# WikiHub-Mini.net
KiCad netlist of a schematic drawn in Altium Designer
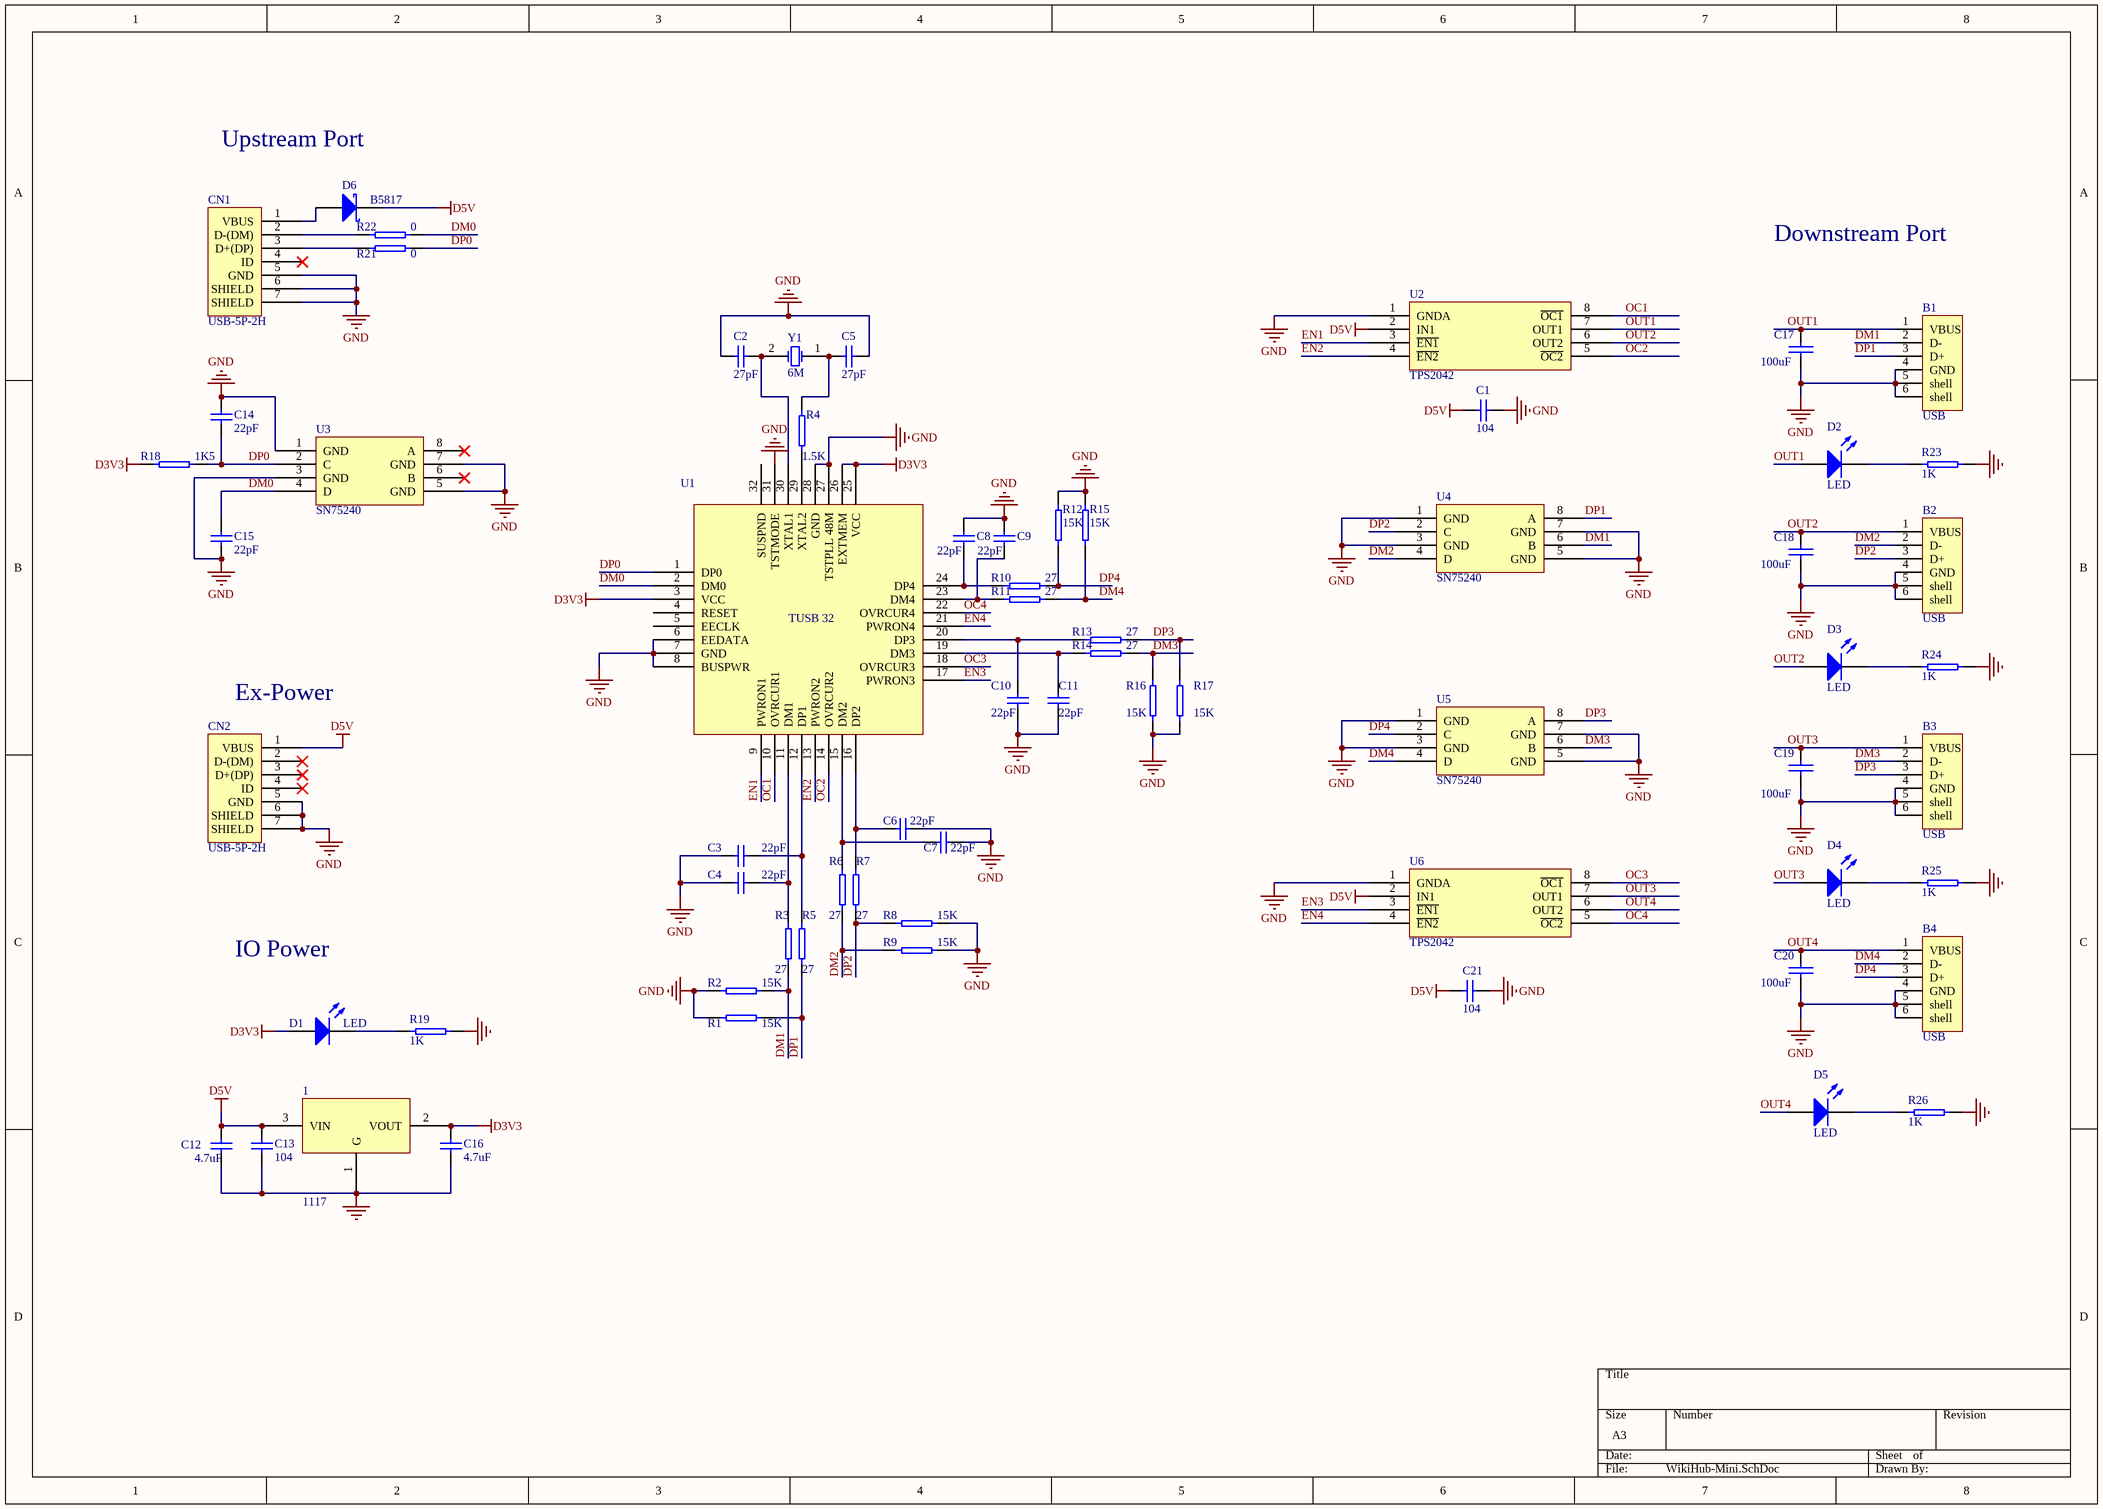
[diagram p0: WikiHub-Mini.SchDoc]

(export (version "E")
  (design (tool "Eeschema 10.0.6"))
  (components
    (comp (ref "1") (value "1117") (footprint "1117") (libsource (lib "原理图封装库") (part "117")))
    (comp (ref "B1") (value "USB") (footprint "USB-A-Female-T2-Lite") (libsource (lib "*") (part "USB")))
    (comp (ref "B2") (value "USB") (footprint "USB-A-Female-T2-Lite") (libsource (lib "*") (part "USB")))
    (comp (ref "B3") (value "USB") (footprint "USB-A-Female-T2-Lite") (libsource (lib "*") (part "USB")))
    (comp (ref "B4") (value "USB") (footprint "USB-A-Female-T2-Lite") (libsource (lib "*") (part "USB")))
    (comp (ref "C1")
      (value "104")
      (footprint "C0603L")
      (description "Capacitor")
      (fields (field (name "Comment") "Cap") (field (name "PUBLISHER") "Altium Limited"))
      (libsource (lib "Miscellaneous Devices") (part "Cap"))
    )
    (comp (ref "C2")
      (value "27pF")
      (footprint "C0603L")
      (description "Capacitor")
      (fields (field (name "PUBLISHER") "Altium Limited"))
      (libsource (lib "Miscellaneous Devices") (part "Cap"))
    )
    (comp (ref "C3")
      (value "22pF")
      (footprint "C0603L")
      (description "Capacitor")
      (fields (field (name "PUBLISHER") "Altium Limited"))
      (libsource (lib "Miscellaneous Devices") (part "Cap"))
    )
    (comp (ref "C4")
      (value "22pF")
      (footprint "C0603L")
      (description "Capacitor")
      (fields (field (name "PUBLISHER") "Altium Limited"))
      (libsource (lib "Miscellaneous Devices") (part "Cap"))
    )
    (comp (ref "C5")
      (value "27pF")
      (footprint "C0603L")
      (description "Capacitor")
      (fields (field (name "PUBLISHER") "Altium Limited"))
      (libsource (lib "Miscellaneous Devices") (part "Cap"))
    )
    (comp (ref "C6")
      (value "22pF")
      (footprint "C0603L")
      (description "Capacitor")
      (fields (field (name "PUBLISHER") "Altium Limited"))
      (libsource (lib "Miscellaneous Devices") (part "Cap"))
    )
    (comp (ref "C7")
      (value "22pF")
      (footprint "C0603L")
      (description "Capacitor")
      (fields (field (name "PUBLISHER") "Altium Limited"))
      (libsource (lib "Miscellaneous Devices") (part "Cap"))
    )
    (comp (ref "C8")
      (value "22pF")
      (footprint "C0603L")
      (description "Capacitor")
      (fields (field (name "PUBLISHER") "Altium Limited"))
      (libsource (lib "Miscellaneous Devices") (part "Cap"))
    )
    (comp (ref "C9")
      (value "22pF")
      (footprint "C0603L")
      (description "Capacitor")
      (fields (field (name "PUBLISHER") "Altium Limited"))
      (libsource (lib "Miscellaneous Devices") (part "Cap"))
    )
    (comp (ref "C10")
      (value "22pF")
      (footprint "C0603L")
      (description "Capacitor")
      (fields (field (name "PUBLISHER") "Altium Limited"))
      (libsource (lib "Miscellaneous Devices") (part "Cap"))
    )
    (comp (ref "C11")
      (value "22pF")
      (footprint "C0603L")
      (description "Capacitor")
      (fields (field (name "PUBLISHER") "Altium Limited"))
      (libsource (lib "Miscellaneous Devices") (part "Cap"))
    )
    (comp (ref "C12")
      (value "4.7uF")
      (footprint "C0603L")
      (description "Capacitor")
      (fields (field (name "Comment") "Cap") (field (name "PUBLISHER") "Altium Limited"))
      (libsource (lib "Miscellaneous Devices") (part "Cap"))
    )
    (comp (ref "C13")
      (value "104")
      (footprint "C0603L")
      (description "Capacitor")
      (fields (field (name "Comment") "Cap") (field (name "PUBLISHER") "Altium Limited"))
      (libsource (lib "Miscellaneous Devices") (part "Cap"))
    )
    (comp (ref "C14")
      (value "22pF")
      (footprint "C0603L")
      (description "Capacitor")
      (fields (field (name "PUBLISHER") "Altium Limited"))
      (libsource (lib "Miscellaneous Devices") (part "Cap"))
    )
    (comp (ref "C15")
      (value "22pF")
      (footprint "C0603L")
      (description "Capacitor")
      (fields (field (name "PUBLISHER") "Altium Limited"))
      (libsource (lib "Miscellaneous Devices") (part "Cap"))
    )
    (comp (ref "C16")
      (value "4.7uF")
      (footprint "C0603L")
      (description "Capacitor")
      (fields (field (name "Comment") "Cap") (field (name "PUBLISHER") "Altium Limited"))
      (libsource (lib "Miscellaneous Devices") (part "Cap"))
    )
    (comp (ref "C17")
      (value "100uF")
      (footprint "1210")
      (description "Capacitor")
      (libsource (lib "*") (part "CAP"))
    )
    (comp (ref "C18")
      (value "100uF")
      (footprint "1210")
      (description "Capacitor")
      (libsource (lib "*") (part "CAP"))
    )
    (comp (ref "C19")
      (value "100uF")
      (footprint "1210")
      (description "Capacitor")
      (libsource (lib "*") (part "CAP"))
    )
    (comp (ref "C20")
      (value "100uF")
      (footprint "1210")
      (description "Capacitor")
      (libsource (lib "*") (part "CAP"))
    )
    (comp (ref "C21")
      (value "104")
      (footprint "C0603L")
      (description "Capacitor")
      (fields (field (name "Comment") "Cap") (field (name "PUBLISHER") "Altium Limited"))
      (libsource (lib "Miscellaneous Devices") (part "Cap"))
    )
    (comp (ref "CN1")
      (value "USB-5P-2H")
      (footprint "USB-B-MICRO-Female-T3")
      (description "USB-M5P-2H")
      (libsource (lib "USB") (part "USB-5P-2H"))
    )
    (comp (ref "CN2")
      (value "USB-5P-2H")
      (footprint "USB-B-MICRO-Female-T3")
      (description "USB-M5P-2H")
      (libsource (lib "USB") (part "USB-5P-2H"))
    )
    (comp (ref "D1")
      (value "LED")
      (footprint "0603pn")
      (description "Typical INFRARED GaAs LED")
      (fields (field (name "PUBLISHER") "Altium Limited"))
      (libsource (lib "Miscellaneous Devices") (part "LED0"))
    )
    (comp (ref "D2")
      (value "LED")
      (footprint "0603pn")
      (description "Typical INFRARED GaAs LED")
      (fields (field (name "PUBLISHER") "Altium Limited"))
      (libsource (lib "Miscellaneous Devices") (part "LED0"))
    )
    (comp (ref "D3")
      (value "LED")
      (footprint "0603pn")
      (description "Typical INFRARED GaAs LED")
      (fields (field (name "PUBLISHER") "Altium Limited"))
      (libsource (lib "Miscellaneous Devices") (part "LED0"))
    )
    (comp (ref "D4")
      (value "LED")
      (footprint "0603pn")
      (description "Typical INFRARED GaAs LED")
      (fields (field (name "PUBLISHER") "Altium Limited"))
      (libsource (lib "Miscellaneous Devices") (part "LED0"))
    )
    (comp (ref "D5")
      (value "LED")
      (footprint "0603pn")
      (description "Typical INFRARED GaAs LED")
      (fields (field (name "PUBLISHER") "Altium Limited"))
      (libsource (lib "Miscellaneous Devices") (part "LED0"))
    )
    (comp (ref "D6")
      (value "B5817")
      (footprint "SOD-123")
      (description "Schottky Diode")
      (fields (field (name "PUBLISHER") "Altium Limited"))
      (libsource (lib "Misc") (part "D Schottky"))
    )
    (comp (ref "R1") (value "15K") (footprint "R0603") (libsource (lib "原理图封装库") (part "RES")))
    (comp (ref "R2") (value "15K") (footprint "R0603") (libsource (lib "原理图封装库") (part "RES")))
    (comp (ref "R3") (value "27") (footprint "R0603") (libsource (lib "原理图封装库") (part "RES")))
    (comp (ref "R4") (value "1.5K") (footprint "R0603") (libsource (lib "原理图封装库") (part "RES")))
    (comp (ref "R5") (value "27") (footprint "R0603") (libsource (lib "原理图封装库") (part "RES")))
    (comp (ref "R6") (value "27") (footprint "R0603") (libsource (lib "原理图封装库") (part "RES")))
    (comp (ref "R7") (value "27") (footprint "R0603") (libsource (lib "原理图封装库") (part "RES")))
    (comp (ref "R8") (value "15K") (footprint "R0603") (libsource (lib "原理图封装库") (part "RES")))
    (comp (ref "R9") (value "15K") (footprint "R0603") (libsource (lib "原理图封装库") (part "RES")))
    (comp (ref "R10") (value "27") (footprint "R0603") (libsource (lib "原理图封装库") (part "RES")))
    (comp (ref "R11") (value "27") (footprint "R0603") (libsource (lib "原理图封装库") (part "RES")))
    (comp (ref "R12") (value "15K") (footprint "R0603") (libsource (lib "原理图封装库") (part "RES")))
    (comp (ref "R13") (value "27") (footprint "R0603") (libsource (lib "原理图封装库") (part "RES")))
    (comp (ref "R14") (value "27") (footprint "R0603") (libsource (lib "原理图封装库") (part "RES")))
    (comp (ref "R15") (value "15K") (footprint "R0603") (libsource (lib "原理图封装库") (part "RES")))
    (comp (ref "R16") (value "15K") (footprint "R0603") (libsource (lib "原理图封装库") (part "RES")))
    (comp (ref "R17") (value "15K") (footprint "R0603") (libsource (lib "原理图封装库") (part "RES")))
    (comp (ref "R18") (value "1K5") (footprint "R0603") (libsource (lib "原理图封装库") (part "RES")))
    (comp (ref "R19") (value "1K") (footprint "R0603") (libsource (lib "原理图封装库") (part "RES")))
    (comp (ref "R21") (value "0") (footprint "R0603") (libsource (lib "原理图封装库") (part "RES")))
    (comp (ref "R22") (value "0") (footprint "R0603") (libsource (lib "原理图封装库") (part "RES")))
    (comp (ref "R23") (value "1K") (footprint "R0603") (libsource (lib "原理图封装库") (part "RES")))
    (comp (ref "R24") (value "1K") (footprint "R0603") (libsource (lib "原理图封装库") (part "RES")))
    (comp (ref "R25") (value "1K") (footprint "R0603") (libsource (lib "原理图封装库") (part "RES")))
    (comp (ref "R26") (value "1K") (footprint "R0603") (libsource (lib "原理图封装库") (part "RES")))
    (comp (ref "U1") (value "TUSB 32") (footprint "TQFP32") (libsource (lib "rhyme-SCH") (part "TUSB 32")))
    (comp (ref "U2") (value "TPS2042") (footprint "SO8W_M") (libsource (lib "WikiHub") (part "TPS2042")))
    (comp (ref "U3")
      (value "SN75240")
      (footprint "SOP8 - 0.65")
      (libsource (lib "rhyme-SCH") (part "SN75240"))
    )
    (comp (ref "U4")
      (value "SN75240")
      (footprint "SOP8 - 0.65")
      (libsource (lib "rhyme-SCH") (part "SN75240"))
    )
    (comp (ref "U5")
      (value "SN75240")
      (footprint "SOP8 - 0.65")
      (libsource (lib "rhyme-SCH") (part "SN75240"))
    )
    (comp (ref "U6") (value "TPS2042") (footprint "SO8W_M") (libsource (lib "WikiHub") (part "TPS2042")))
    (comp (ref "Y1")
      (value "6M")
      (footprint "XTAL")
      (description "Crystal Oscillator")
      (fields (field (name "PUBLISHER") "Altium Limited"))
      (libsource (lib "Miscellaneous Devices") (part "XTAL"))
    )
  )
  (nets
    (net (code "1") (name "/DM0") (class "Default")
      (node (ref "C15") (pin "1") (pinfunction "1_1") (pintype "passive"))
      (node (ref "R22") (pin "1") (pinfunction "1_1") (pintype "passive"))
      (node (ref "U1") (pin "2") (pinfunction "DM0_2") (pintype "passive"))
      (node (ref "U3") (pin "4") (pinfunction "D_4") (pintype "passive"))
    )
    (net (code "2") (name "/DM1") (class "Default")
      (node (ref "B1") (pin "2") (pinfunction "D-_2") (pintype "passive"))
      (node (ref "R2") (pin "1") (pinfunction "1_1") (pintype "passive"))
      (node (ref "R3") (pin "1") (pinfunction "1_1") (pintype "passive"))
      (node (ref "U4") (pin "6") (pinfunction "B_6") (pintype "passive"))
    )
    (net (code "3") (name "/DM2") (class "Default")
      (node (ref "B2") (pin "2") (pinfunction "D-_2") (pintype "passive"))
      (node (ref "R6") (pin "1") (pinfunction "1_1") (pintype "passive"))
      (node (ref "R9") (pin "2") (pinfunction "2_2") (pintype "passive"))
      (node (ref "U4") (pin "4") (pinfunction "D_4") (pintype "passive"))
    )
    (net (code "4") (name "/DM3") (class "Default")
      (node (ref "B3") (pin "2") (pinfunction "D-_2") (pintype "passive"))
      (node (ref "R14") (pin "1") (pinfunction "1_1") (pintype "passive"))
      (node (ref "R16") (pin "1") (pinfunction "1_1") (pintype "passive"))
      (node (ref "U5") (pin "6") (pinfunction "B_6") (pintype "passive"))
    )
    (net (code "5") (name "/DM4") (class "Default")
      (node (ref "B4") (pin "2") (pinfunction "D-_2") (pintype "passive"))
      (node (ref "R11") (pin "1") (pinfunction "1_1") (pintype "passive"))
      (node (ref "R15") (pin "2") (pinfunction "2_2") (pintype "passive"))
      (node (ref "U5") (pin "4") (pinfunction "D_4") (pintype "passive"))
    )
    (net (code "6") (name "/DP0") (class "Default")
      (node (ref "C14") (pin "2") (pinfunction "2_2") (pintype "passive"))
      (node (ref "R18") (pin "1") (pinfunction "1_1") (pintype "passive"))
      (node (ref "R21") (pin "1") (pinfunction "1_1") (pintype "passive"))
      (node (ref "U1") (pin "1") (pinfunction "DP0_1") (pintype "passive"))
      (node (ref "U3") (pin "2") (pinfunction "C_2") (pintype "passive"))
    )
    (net (code "7") (name "/DP1") (class "Default")
      (node (ref "B1") (pin "3") (pinfunction "D+_3") (pintype "passive"))
      (node (ref "R1") (pin "1") (pinfunction "1_1") (pintype "passive"))
      (node (ref "R5") (pin "1") (pinfunction "1_1") (pintype "passive"))
      (node (ref "U4") (pin "8") (pinfunction "A_8") (pintype "passive"))
    )
    (net (code "8") (name "/DP2") (class "Default")
      (node (ref "B2") (pin "3") (pinfunction "D+_3") (pintype "passive"))
      (node (ref "R7") (pin "1") (pinfunction "1_1") (pintype "passive"))
      (node (ref "R8") (pin "2") (pinfunction "2_2") (pintype "passive"))
      (node (ref "U4") (pin "2") (pinfunction "C_2") (pintype "passive"))
    )
    (net (code "9") (name "/DP3") (class "Default")
      (node (ref "B3") (pin "3") (pinfunction "D+_3") (pintype "passive"))
      (node (ref "R13") (pin "1") (pinfunction "1_1") (pintype "passive"))
      (node (ref "R17") (pin "1") (pinfunction "1_1") (pintype "passive"))
      (node (ref "U5") (pin "8") (pinfunction "A_8") (pintype "passive"))
    )
    (net (code "10") (name "/DP4") (class "Default")
      (node (ref "B4") (pin "3") (pinfunction "D+_3") (pintype "passive"))
      (node (ref "R10") (pin "1") (pinfunction "1_1") (pintype "passive"))
      (node (ref "R12") (pin "2") (pinfunction "2_2") (pintype "passive"))
      (node (ref "U5") (pin "2") (pinfunction "C_2") (pintype "passive"))
    )
    (net (code "11") (name "/EN1") (class "Default")
      (node (ref "U1") (pin "9") (pinfunction "PWRON1_9") (pintype "passive"))
      (node (ref "U2") (pin "3") (pinfunction "~{EN1}_3") (pintype "passive"))
    )
    (net (code "12") (name "/EN2") (class "Default")
      (node (ref "U1") (pin "13") (pinfunction "PWRON2_13") (pintype "passive"))
      (node (ref "U2") (pin "4") (pinfunction "~{EN2}_4") (pintype "passive"))
    )
    (net (code "13") (name "/EN3") (class "Default")
      (node (ref "U1") (pin "17") (pinfunction "PWRON3_17") (pintype "passive"))
      (node (ref "U6") (pin "3") (pinfunction "~{EN1}_3") (pintype "passive"))
    )
    (net (code "14") (name "/EN4") (class "Default")
      (node (ref "U1") (pin "21") (pinfunction "PWRON4_21") (pintype "passive"))
      (node (ref "U6") (pin "4") (pinfunction "~{EN2}_4") (pintype "passive"))
    )
    (net (code "15") (name "/OC1") (class "Default")
      (node (ref "U1") (pin "10") (pinfunction "OVRCUR1_10") (pintype "passive"))
      (node (ref "U2") (pin "8") (pinfunction "~{OC1}_8") (pintype "passive"))
    )
    (net (code "16") (name "/OC2") (class "Default")
      (node (ref "U1") (pin "14") (pinfunction "OVRCUR2_14") (pintype "passive"))
      (node (ref "U2") (pin "5") (pinfunction "~{OC2}_5") (pintype "passive"))
    )
    (net (code "17") (name "/OC3") (class "Default")
      (node (ref "U1") (pin "18") (pinfunction "OVRCUR3_18") (pintype "passive"))
      (node (ref "U6") (pin "8") (pinfunction "~{OC1}_8") (pintype "passive"))
    )
    (net (code "18") (name "/OC4") (class "Default")
      (node (ref "U1") (pin "22") (pinfunction "OVRCUR4_22") (pintype "passive"))
      (node (ref "U6") (pin "5") (pinfunction "~{OC2}_5") (pintype "passive"))
    )
    (net (code "19") (name "/OUT1") (class "Default")
      (node (ref "B1") (pin "1") (pinfunction "VBUS_1") (pintype "passive"))
      (node (ref "C17") (pin "1") (pinfunction "1_1") (pintype "passive"))
      (node (ref "D2") (pin "1") (pinfunction "A_1") (pintype "passive"))
      (node (ref "U2") (pin "7") (pinfunction "OUT1_7") (pintype "passive"))
    )
    (net (code "20") (name "/OUT2") (class "Default")
      (node (ref "B2") (pin "1") (pinfunction "VBUS_1") (pintype "passive"))
      (node (ref "C18") (pin "1") (pinfunction "1_1") (pintype "passive"))
      (node (ref "D3") (pin "1") (pinfunction "A_1") (pintype "passive"))
      (node (ref "U2") (pin "6") (pinfunction "OUT2_6") (pintype "passive"))
    )
    (net (code "21") (name "/OUT3") (class "Default")
      (node (ref "B3") (pin "1") (pinfunction "VBUS_1") (pintype "passive"))
      (node (ref "C19") (pin "1") (pinfunction "1_1") (pintype "passive"))
      (node (ref "D4") (pin "1") (pinfunction "A_1") (pintype "passive"))
      (node (ref "U6") (pin "7") (pinfunction "OUT1_7") (pintype "passive"))
    )
    (net (code "22") (name "/OUT4") (class "Default")
      (node (ref "B4") (pin "1") (pinfunction "VBUS_1") (pintype "passive"))
      (node (ref "C20") (pin "1") (pinfunction "1_1") (pintype "passive"))
      (node (ref "D5") (pin "1") (pinfunction "A_1") (pintype "passive"))
      (node (ref "U6") (pin "6") (pinfunction "OUT2_6") (pintype "passive"))
    )
    (net (code "23") (name "D3V3") (class "Default")
      (node (ref "1") (pin "2") (pinfunction "VOUT_2") (pintype "passive"))
      (node (ref "C16") (pin "2") (pinfunction "2_2") (pintype "passive"))
      (node (ref "D1") (pin "1") (pinfunction "A_1") (pintype "passive"))
      (node (ref "R18") (pin "2") (pinfunction "2_2") (pintype "passive"))
      (node (ref "U1") (pin "25") (pinfunction "VCC_25") (pintype "passive"))
      (node (ref "U1") (pin "26") (pinfunction "EXTMEM_26") (pintype "passive"))
      (node (ref "U1") (pin "3") (pinfunction "VCC_3") (pintype "passive"))
    )
    (net (code "24") (name "D5V") (class "Default")
      (node (ref "1") (pin "3") (pinfunction "VIN_3") (pintype "passive"))
      (node (ref "C1") (pin "2") (pinfunction "2_2") (pintype "passive"))
      (node (ref "C12") (pin "2") (pinfunction "2_2") (pintype "passive"))
      (node (ref "C13") (pin "2") (pinfunction "2_2") (pintype "passive"))
      (node (ref "C21") (pin "2") (pinfunction "2_2") (pintype "passive"))
      (node (ref "CN2") (pin "1") (pinfunction "VBUS_1") (pintype "passive"))
      (node (ref "D6") (pin "2") (pinfunction "K_2") (pintype "passive"))
      (node (ref "U2") (pin "2") (pinfunction "IN1_2") (pintype "passive"))
      (node (ref "U6") (pin "2") (pinfunction "IN1_2") (pintype "passive"))
    )
    (net (code "25") (name "GND") (class "Default")
      (node (ref "1") (pin "1") (pinfunction "G_1") (pintype "passive"))
      (node (ref "B1") (pin "4") (pinfunction "GND_4") (pintype "passive"))
      (node (ref "B1") (pin "5") (pinfunction "shell_5") (pintype "passive"))
      (node (ref "B1") (pin "6") (pinfunction "shell_6") (pintype "passive"))
      (node (ref "B2") (pin "4") (pinfunction "GND_4") (pintype "passive"))
      (node (ref "B2") (pin "5") (pinfunction "shell_5") (pintype "passive"))
      (node (ref "B2") (pin "6") (pinfunction "shell_6") (pintype "passive"))
      (node (ref "B3") (pin "4") (pinfunction "GND_4") (pintype "passive"))
      (node (ref "B3") (pin "5") (pinfunction "shell_5") (pintype "passive"))
      (node (ref "B3") (pin "6") (pinfunction "shell_6") (pintype "passive"))
      (node (ref "B4") (pin "4") (pinfunction "GND_4") (pintype "passive"))
      (node (ref "B4") (pin "5") (pinfunction "shell_5") (pintype "passive"))
      (node (ref "B4") (pin "6") (pinfunction "shell_6") (pintype "passive"))
      (node (ref "C1") (pin "1") (pinfunction "1_1") (pintype "passive"))
      (node (ref "C10") (pin "1") (pinfunction "1_1") (pintype "passive"))
      (node (ref "C11") (pin "1") (pinfunction "1_1") (pintype "passive"))
      (node (ref "C12") (pin "1") (pinfunction "1_1") (pintype "passive"))
      (node (ref "C13") (pin "1") (pinfunction "1_1") (pintype "passive"))
      (node (ref "C14") (pin "1") (pinfunction "1_1") (pintype "passive"))
      (node (ref "C15") (pin "2") (pinfunction "2_2") (pintype "passive"))
      (node (ref "C16") (pin "1") (pinfunction "1_1") (pintype "passive"))
      (node (ref "C17") (pin "2") (pinfunction "2_2") (pintype "passive"))
      (node (ref "C18") (pin "2") (pinfunction "2_2") (pintype "passive"))
      (node (ref "C19") (pin "2") (pinfunction "2_2") (pintype "passive"))
      (node (ref "C2") (pin "2") (pinfunction "2_2") (pintype "passive"))
      (node (ref "C20") (pin "2") (pinfunction "2_2") (pintype "passive"))
      (node (ref "C21") (pin "1") (pinfunction "1_1") (pintype "passive"))
      (node (ref "C3") (pin "1") (pinfunction "1_1") (pintype "passive"))
      (node (ref "C4") (pin "1") (pinfunction "1_1") (pintype "passive"))
      (node (ref "C5") (pin "2") (pinfunction "2_2") (pintype "passive"))
      (node (ref "C6") (pin "2") (pinfunction "2_2") (pintype "passive"))
      (node (ref "C7") (pin "2") (pinfunction "2_2") (pintype "passive"))
      (node (ref "C8") (pin "2") (pinfunction "2_2") (pintype "passive"))
      (node (ref "C9") (pin "2") (pinfunction "2_2") (pintype "passive"))
      (node (ref "CN1") (pin "5") (pinfunction "GND_5") (pintype "passive"))
      (node (ref "CN1") (pin "6") (pinfunction "SHIELD_6") (pintype "passive"))
      (node (ref "CN1") (pin "7") (pinfunction "SHIELD_7") (pintype "passive"))
      (node (ref "CN2") (pin "5") (pinfunction "GND_5") (pintype "passive"))
      (node (ref "CN2") (pin "6") (pinfunction "SHIELD_6") (pintype "passive"))
      (node (ref "CN2") (pin "7") (pinfunction "SHIELD_7") (pintype "passive"))
      (node (ref "R1") (pin "2") (pinfunction "2_2") (pintype "passive"))
      (node (ref "R12") (pin "1") (pinfunction "1_1") (pintype "passive"))
      (node (ref "R15") (pin "1") (pinfunction "1_1") (pintype "passive"))
      (node (ref "R16") (pin "2") (pinfunction "2_2") (pintype "passive"))
      (node (ref "R17") (pin "2") (pinfunction "2_2") (pintype "passive"))
      (node (ref "R19") (pin "1") (pinfunction "1_1") (pintype "passive"))
      (node (ref "R2") (pin "2") (pinfunction "2_2") (pintype "passive"))
      (node (ref "R23") (pin "1") (pinfunction "1_1") (pintype "passive"))
      (node (ref "R24") (pin "1") (pinfunction "1_1") (pintype "passive"))
      (node (ref "R25") (pin "1") (pinfunction "1_1") (pintype "passive"))
      (node (ref "R26") (pin "1") (pinfunction "1_1") (pintype "passive"))
      (node (ref "R8") (pin "1") (pinfunction "1_1") (pintype "passive"))
      (node (ref "R9") (pin "1") (pinfunction "1_1") (pintype "passive"))
      (node (ref "U1") (pin "27") (pinfunction "TSTPLL_48M_27") (pintype "passive"))
      (node (ref "U1") (pin "28") (pinfunction "GND_28") (pintype "passive"))
      (node (ref "U1") (pin "31") (pinfunction "TSTMODE_31") (pintype "passive"))
      (node (ref "U1") (pin "6") (pinfunction "EEDATA_6") (pintype "passive"))
      (node (ref "U1") (pin "7") (pinfunction "GND_7") (pintype "passive"))
      (node (ref "U1") (pin "8") (pinfunction "BUSPWR_8") (pintype "passive"))
      (node (ref "U2") (pin "1") (pinfunction "GNDA_1") (pintype "passive"))
      (node (ref "U3") (pin "1") (pinfunction "GND_1") (pintype "passive"))
      (node (ref "U3") (pin "3") (pinfunction "GND_3") (pintype "passive"))
      (node (ref "U3") (pin "5") (pinfunction "GND_5") (pintype "passive"))
      (node (ref "U3") (pin "7") (pinfunction "GND_7") (pintype "passive"))
      (node (ref "U4") (pin "1") (pinfunction "GND_1") (pintype "passive"))
      (node (ref "U4") (pin "3") (pinfunction "GND_3") (pintype "passive"))
      (node (ref "U4") (pin "5") (pinfunction "GND_5") (pintype "passive"))
      (node (ref "U4") (pin "7") (pinfunction "GND_7") (pintype "passive"))
      (node (ref "U5") (pin "1") (pinfunction "GND_1") (pintype "passive"))
      (node (ref "U5") (pin "3") (pinfunction "GND_3") (pintype "passive"))
      (node (ref "U5") (pin "5") (pinfunction "GND_5") (pintype "passive"))
      (node (ref "U5") (pin "7") (pinfunction "GND_7") (pintype "passive"))
      (node (ref "U6") (pin "1") (pinfunction "GNDA_1") (pintype "passive"))
    )
    (net (code "26") (name "Net-(CN1-D+(DP))") (class "Default")
      (node (ref "CN1") (pin "3") (pinfunction "D+(DP)_3") (pintype "passive"))
      (node (ref "R21") (pin "2") (pinfunction "2_2") (pintype "passive"))
    )
    (net (code "27") (name "Net-(CN1-D-(DM))") (class "Default")
      (node (ref "CN1") (pin "2") (pinfunction "D-(DM)_2") (pintype "passive"))
      (node (ref "R22") (pin "2") (pinfunction "2_2") (pintype "passive"))
    )
    (net (code "28") (name "Net-(CN1-VBUS)") (class "Default")
      (node (ref "CN1") (pin "1") (pinfunction "VBUS_1") (pintype "passive"))
      (node (ref "D6") (pin "1") (pinfunction "A_1") (pintype "passive"))
    )
    (net (code "29") (name "Net-(D1-K)") (class "Default")
      (node (ref "D1") (pin "2") (pinfunction "K_2") (pintype "passive"))
      (node (ref "R19") (pin "2") (pinfunction "2_2") (pintype "passive"))
    )
    (net (code "30") (name "Net-(D2-K)") (class "Default")
      (node (ref "D2") (pin "2") (pinfunction "K_2") (pintype "passive"))
      (node (ref "R23") (pin "2") (pinfunction "2_2") (pintype "passive"))
    )
    (net (code "31") (name "Net-(D3-K)") (class "Default")
      (node (ref "D3") (pin "2") (pinfunction "K_2") (pintype "passive"))
      (node (ref "R24") (pin "2") (pinfunction "2_2") (pintype "passive"))
    )
    (net (code "32") (name "Net-(D4-K)") (class "Default")
      (node (ref "D4") (pin "2") (pinfunction "K_2") (pintype "passive"))
      (node (ref "R25") (pin "2") (pinfunction "2_2") (pintype "passive"))
    )
    (net (code "33") (name "Net-(D5-K)") (class "Default")
      (node (ref "D5") (pin "2") (pinfunction "K_2") (pintype "passive"))
      (node (ref "R26") (pin "2") (pinfunction "2_2") (pintype "passive"))
    )
    (net (code "34") (name "Net-(U1-DM1)") (class "Default")
      (node (ref "C4") (pin "2") (pinfunction "2_2") (pintype "passive"))
      (node (ref "R3") (pin "2") (pinfunction "2_2") (pintype "passive"))
      (node (ref "U1") (pin "11") (pinfunction "DM1_11") (pintype "passive"))
    )
    (net (code "35") (name "Net-(U1-DM2)") (class "Default")
      (node (ref "C7") (pin "1") (pinfunction "1_1") (pintype "passive"))
      (node (ref "R6") (pin "2") (pinfunction "2_2") (pintype "passive"))
      (node (ref "U1") (pin "15") (pinfunction "DM2_15") (pintype "passive"))
    )
    (net (code "36") (name "Net-(U1-DM3)") (class "Default")
      (node (ref "C11") (pin "2") (pinfunction "2_2") (pintype "passive"))
      (node (ref "R14") (pin "2") (pinfunction "2_2") (pintype "passive"))
      (node (ref "U1") (pin "19") (pinfunction "DM3_19") (pintype "passive"))
    )
    (net (code "37") (name "Net-(U1-DM4)") (class "Default")
      (node (ref "C9") (pin "1") (pinfunction "1_1") (pintype "passive"))
      (node (ref "R11") (pin "2") (pinfunction "2_2") (pintype "passive"))
      (node (ref "U1") (pin "23") (pinfunction "DM4_23") (pintype "passive"))
    )
    (net (code "38") (name "Net-(U1-DP1)") (class "Default")
      (node (ref "C3") (pin "2") (pinfunction "2_2") (pintype "passive"))
      (node (ref "R5") (pin "2") (pinfunction "2_2") (pintype "passive"))
      (node (ref "U1") (pin "12") (pinfunction "DP1_12") (pintype "passive"))
    )
    (net (code "39") (name "Net-(U1-DP2)") (class "Default")
      (node (ref "C6") (pin "1") (pinfunction "1_1") (pintype "passive"))
      (node (ref "R7") (pin "2") (pinfunction "2_2") (pintype "passive"))
      (node (ref "U1") (pin "16") (pinfunction "DP2_16") (pintype "passive"))
    )
    (net (code "40") (name "Net-(U1-DP3)") (class "Default")
      (node (ref "C10") (pin "2") (pinfunction "2_2") (pintype "passive"))
      (node (ref "R13") (pin "2") (pinfunction "2_2") (pintype "passive"))
      (node (ref "U1") (pin "20") (pinfunction "DP3_20") (pintype "passive"))
    )
    (net (code "41") (name "Net-(U1-DP4)") (class "Default")
      (node (ref "C8") (pin "1") (pinfunction "1_1") (pintype "passive"))
      (node (ref "R10") (pin "2") (pinfunction "2_2") (pintype "passive"))
      (node (ref "U1") (pin "24") (pinfunction "DP4_24") (pintype "passive"))
    )
    (net (code "42") (name "Net-(U1-XTAL1)") (class "Default")
      (node (ref "C2") (pin "1") (pinfunction "1_1") (pintype "passive"))
      (node (ref "U1") (pin "30") (pinfunction "XTAL1_30") (pintype "passive"))
      (node (ref "Y1") (pin "2") (pinfunction "OSC2_2") (pintype "passive"))
    )
    (net (code "43") (name "Net-(U1-XTAL2)") (class "Default")
      (node (ref "R4") (pin "2") (pinfunction "2_2") (pintype "passive"))
      (node (ref "U1") (pin "29") (pinfunction "XTAL2_29") (pintype "passive"))
    )
    (net (code "44") (name "Net-(Y1-OSC1)") (class "Default")
      (node (ref "C5") (pin "1") (pinfunction "1_1") (pintype "passive"))
      (node (ref "R4") (pin "1") (pinfunction "1_1") (pintype "passive"))
      (node (ref "Y1") (pin "1") (pinfunction "OSC1_1") (pintype "passive"))
    )
    (net (code "45") (name "unconnected-(CN1-ID-Pad4)") (class "Default")
      (node (ref "CN1") (pin "4") (pinfunction "ID_4") (pintype "passive+no_connect"))
    )
    (net (code "46") (name "unconnected-(CN2-D+(DP)-Pad3)") (class "Default")
      (node (ref "CN2") (pin "3") (pinfunction "D+(DP)_3") (pintype "passive+no_connect"))
    )
    (net (code "47") (name "unconnected-(CN2-D-(DM)-Pad2)") (class "Default")
      (node (ref "CN2") (pin "2") (pinfunction "D-(DM)_2") (pintype "passive+no_connect"))
    )
    (net (code "48") (name "unconnected-(CN2-ID-Pad4)") (class "Default")
      (node (ref "CN2") (pin "4") (pinfunction "ID_4") (pintype "passive+no_connect"))
    )
    (net (code "49") (name "unconnected-(U1-EECLK-Pad5)") (class "Default")
      (node (ref "U1") (pin "5") (pinfunction "EECLK_5") (pintype "passive"))
    )
    (net (code "50") (name "unconnected-(U1-RESET-Pad4)") (class "Default")
      (node (ref "U1") (pin "4") (pinfunction "RESET_4") (pintype "passive"))
    )
    (net (code "51") (name "unconnected-(U1-SUSPND-Pad32)") (class "Default")
      (node (ref "U1") (pin "32") (pinfunction "SUSPND_32") (pintype "passive"))
    )
    (net (code "52") (name "unconnected-(U3-A-Pad8)") (class "Default")
      (node (ref "U3") (pin "8") (pinfunction "A_8") (pintype "passive+no_connect"))
    )
    (net (code "53") (name "unconnected-(U3-B-Pad6)") (class "Default")
      (node (ref "U3") (pin "6") (pinfunction "B_6") (pintype "passive+no_connect"))
    )
  )
)
